# SparkFun_Qwiic_FS3000_top.net
KiCad netlist of a schematic drawn in EAGLE
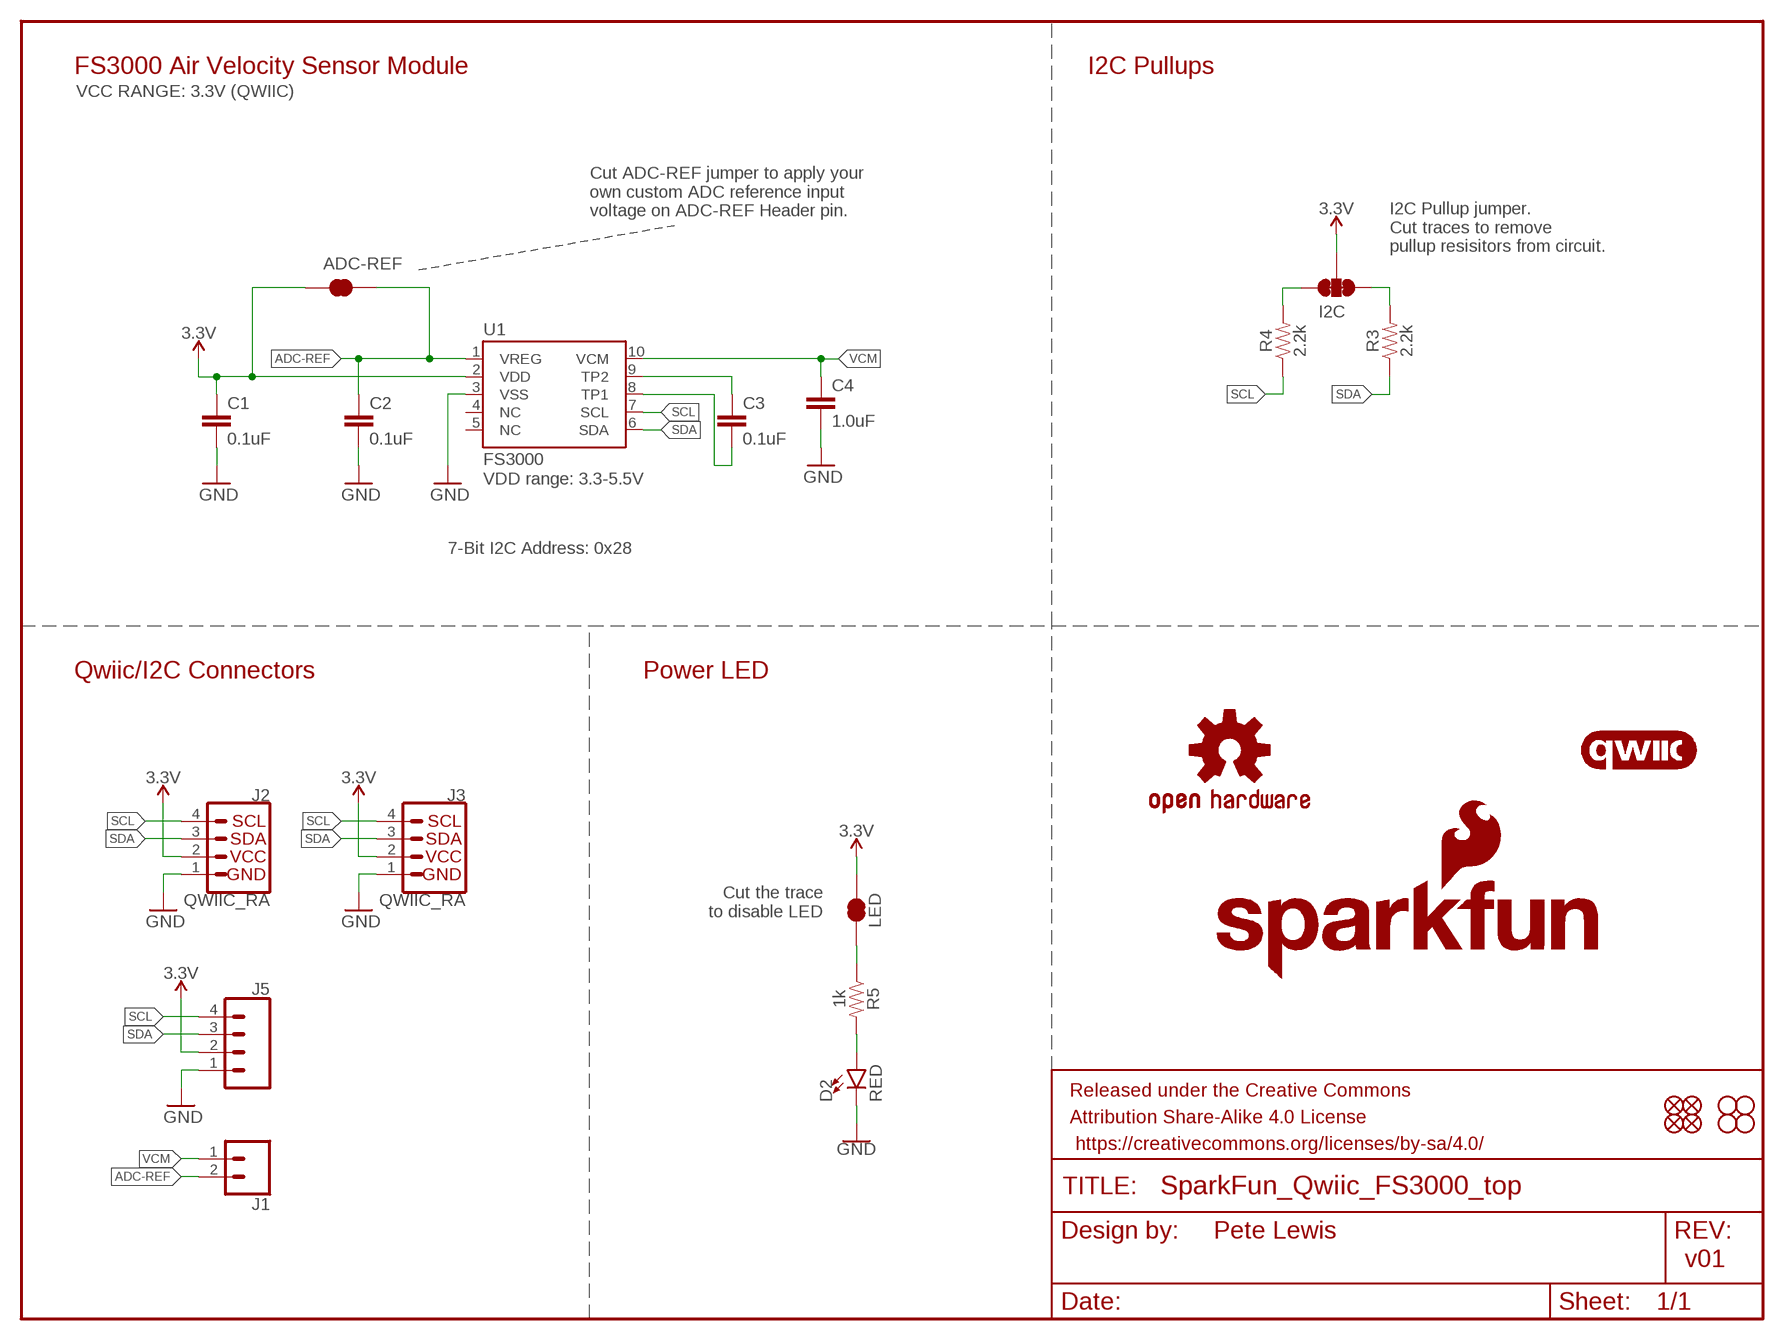
[diagram p0: schematic, sheet 1]

(export (version "E")
  (design (tool "Eeschema 10.0.6"))
  (components
    (comp (ref "ADC-REF")
      (value "JUMPER-SMT_2_NC_TRACE_SILK")
      (footprint "eagle-import:SMT-JUMPER_2_NC_TRACE_SILK")
      (libsource (lib "eagle-import") (part "JUMPER-SMT_2_NC_TRACE_SILK"))
    )
    (comp (ref "C1")
      (value "0.1uF")
      (footprint "eagle-import:0402-TIGHT")
      (libsource (lib "eagle-import") (part "0.1UF-0402T-16V-10%"))
    )
    (comp (ref "C2")
      (value "0.1uF")
      (footprint "eagle-import:0402-TIGHT")
      (libsource (lib "eagle-import") (part "0.1UF-0402T-16V-10%"))
    )
    (comp (ref "C3")
      (value "0.1uF")
      (footprint "eagle-import:0402-TIGHT")
      (libsource (lib "eagle-import") (part "0.1UF-0402T-16V-10%"))
    )
    (comp (ref "C4")
      (value "1.0uF")
      (footprint "eagle-import:0402-TIGHT")
      (libsource (lib "eagle-import") (part "1.0UF-0402T-16V-10%"))
    )
    (comp (ref "D2")
      (value "RED")
      (footprint "eagle-import:LED-0603")
      (libsource (lib "eagle-import") (part "LED-RED0603"))
    )
    (comp (ref "FRAME1")
      (value "FRAME-LETTER")
      (footprint "eagle-import:CREATIVE_COMMONS")
      (libsource (lib "eagle-import") (part "FRAME-LETTER"))
    )
    (comp (ref "I2C")
      (value "JUMPER-SMT_3_2-NC_TRACE_SILK")
      (footprint "eagle-import:SMT-JUMPER_3_2-NC_TRACE_SILK")
      (libsource (lib "eagle-import") (part "JUMPER-SMT_3_2-NC_TRACE_SILK"))
    )
    (comp (ref "J1")
      (value "CONN_021X02_NO_SILK")
      (footprint "eagle-import:1X02_NO_SILK")
      (libsource (lib "eagle-import") (part "CONN_021X02_NO_SILK"))
    )
    (comp (ref "J2")
      (value "QWIIC_RA")
      (footprint "eagle-import:JST04_1MM_RA")
      (libsource (lib "eagle-import") (part "QWIIC_CONNECTORJS-1MM"))
    )
    (comp (ref "J3")
      (value "QWIIC_RA")
      (footprint "eagle-import:JST04_1MM_RA")
      (libsource (lib "eagle-import") (part "QWIIC_CONNECTORJS-1MM"))
    )
    (comp (ref "J5")
      (value "CONN_041X04_NO_SILK")
      (footprint "eagle-import:1X04_NO_SILK")
      (libsource (lib "eagle-import") (part "CONN_041X04_NO_SILK"))
    )
    (comp (ref "JP1")
      (value "LED")
      (footprint "eagle-import:SMT-JUMPER_2_NC_TRACE_SILK")
      (libsource (lib "eagle-import") (part "JUMPER-SMT_2_NC_TRACE_SILK"))
    )
    (comp (ref "JP2")
      (value "FIDUCIALUFIDUCIAL")
      (footprint "eagle-import:MICRO-FIDUCIAL")
      (libsource (lib "eagle-import") (part "FIDUCIALUFIDUCIAL"))
    )
    (comp (ref "JP3")
      (value "STAND-OFF")
      (footprint "eagle-import:STAND-OFF")
      (libsource (lib "eagle-import") (part "STAND-OFF"))
    )
    (comp (ref "JP4")
      (value "STAND-OFF")
      (footprint "eagle-import:STAND-OFF")
      (libsource (lib "eagle-import") (part "STAND-OFF"))
    )
    (comp (ref "JP5")
      (value "FIDUCIALUFIDUCIAL")
      (footprint "eagle-import:MICRO-FIDUCIAL")
      (libsource (lib "eagle-import") (part "FIDUCIALUFIDUCIAL"))
    )
    (comp (ref "JP6")
      (value "FIDUCIALUFIDUCIAL")
      (footprint "eagle-import:MICRO-FIDUCIAL")
      (libsource (lib "eagle-import") (part "FIDUCIALUFIDUCIAL"))
    )
    (comp (ref "JP7")
      (value "STAND-OFF")
      (footprint "eagle-import:STAND-OFF")
      (libsource (lib "eagle-import") (part "STAND-OFF"))
    )
    (comp (ref "JP8")
      (value "STAND-OFF")
      (footprint "eagle-import:STAND-OFF")
      (libsource (lib "eagle-import") (part "STAND-OFF"))
    )
    (comp (ref "JP11")
      (value "FIDUCIALUFIDUCIAL")
      (footprint "eagle-import:MICRO-FIDUCIAL")
      (libsource (lib "eagle-import") (part "FIDUCIALUFIDUCIAL"))
    )
    (comp (ref "LOGO1")
      (value "OSHW-LOGOMINI")
      (footprint "eagle-import:OSHW-LOGO-MINI")
      (libsource (lib "eagle-import") (part "OSHW-LOGOMINI"))
    )
    (comp (ref "LOGO3")
      (value "SFE_LOGO_NAME_FLAME.1_INCH")
      (footprint "eagle-import:SFE_LOGO_NAME_FLAME_.1")
      (libsource (lib "eagle-import") (part "SFE_LOGO_NAME_FLAME.1_INCH"))
    )
    (comp (ref "LOGO4")
      (value "QWIIC_LOGO_5MM")
      (footprint "eagle-import:QWIIC_5MM")
      (libsource (lib "eagle-import") (part "QWIIC_LOGO_5MM"))
    )
    (comp (ref "LOGO5")
      (value "SFE_LOGO_NAME_FLAME.1_INCH")
      (footprint "eagle-import:SFE_LOGO_NAME_FLAME_.1")
      (libsource (lib "eagle-import") (part "SFE_LOGO_NAME_FLAME.1_INCH"))
    )
    (comp (ref "R3")
      (value "2.2k")
      (footprint "eagle-import:0402-TIGHT")
      (libsource (lib "eagle-import") (part "2.2KOHM-0402T-1/16W-1%"))
    )
    (comp (ref "R4")
      (value "2.2k")
      (footprint "eagle-import:0402-TIGHT")
      (libsource (lib "eagle-import") (part "2.2KOHM-0402T-1/16W-1%"))
    )
    (comp (ref "R5")
      (value "1k")
      (footprint "eagle-import:0402-TIGHT")
      (libsource (lib "eagle-import") (part "1KOHM-0402T-1/16W-1%"))
    )
    (comp (ref "U1")
      (value "FS3000")
      (footprint "eagle-import:FS3000")
      (libsource (lib "eagle-import") (part "FS3000"))
    )
  )
  (nets
    (net (code "1") (name "3.3V") (class "Default")
      (node (ref "ADC-REF") (pin "1") (pinfunction "1_1") (pintype "passive"))
      (node (ref "C1") (pin "1") (pinfunction "1_1") (pintype "passive"))
      (node (ref "I2C") (pin "2") (pinfunction "2_2") (pintype "passive"))
      (node (ref "J2") (pin "2") (pinfunction "2_2") (pintype "power_in"))
      (node (ref "J3") (pin "2") (pinfunction "2_2") (pintype "power_in"))
      (node (ref "J5") (pin "2") (pinfunction "2_2") (pintype "passive"))
      (node (ref "JP1") (pin "2") (pinfunction "2_2") (pintype "passive"))
      (node (ref "U1") (pin "2") (pinfunction "VDD_2") (pintype "bidirectional"))
    )
    (net (code "2") (name "ADC-REF") (class "Default")
      (node (ref "ADC-REF") (pin "2") (pinfunction "2_2") (pintype "passive"))
      (node (ref "C2") (pin "1") (pinfunction "1_1") (pintype "passive"))
      (node (ref "J1") (pin "2") (pinfunction "2_2") (pintype "passive"))
      (node (ref "U1") (pin "1") (pinfunction "VREG_1") (pintype "bidirectional"))
    )
    (net (code "3") (name "GND") (class "Default")
      (node (ref "C1") (pin "2") (pinfunction "2_2") (pintype "passive"))
      (node (ref "C2") (pin "2") (pinfunction "2_2") (pintype "passive"))
      (node (ref "C4") (pin "2") (pinfunction "2_2") (pintype "passive"))
      (node (ref "D2") (pin "C") (pinfunction "C_C") (pintype "passive"))
      (node (ref "J2") (pin "1") (pinfunction "1_1") (pintype "power_in"))
      (node (ref "J3") (pin "1") (pinfunction "1_1") (pintype "power_in"))
      (node (ref "J5") (pin "1") (pinfunction "1_1") (pintype "passive"))
      (node (ref "U1") (pin "3") (pinfunction "VSS_3") (pintype "bidirectional"))
    )
    (net (code "4") (name "Net-(D2-PadA)") (class "Default")
      (node (ref "D2") (pin "A") (pinfunction "A_A") (pintype "passive"))
      (node (ref "R5") (pin "2") (pinfunction "2_2") (pintype "passive"))
    )
    (net (code "5") (name "Net-(I2C-Pad1)") (class "Default")
      (node (ref "I2C") (pin "1") (pinfunction "1_1") (pintype "passive"))
      (node (ref "R3") (pin "2") (pinfunction "2_2") (pintype "passive"))
    )
    (net (code "6") (name "Net-(I2C-Pad3)") (class "Default")
      (node (ref "I2C") (pin "3") (pinfunction "3_3") (pintype "passive"))
      (node (ref "R4") (pin "2") (pinfunction "2_2") (pintype "passive"))
    )
    (net (code "7") (name "Net-(JP1-Pad1)") (class "Default")
      (node (ref "JP1") (pin "1") (pinfunction "1_1") (pintype "passive"))
      (node (ref "R5") (pin "1") (pinfunction "1_1") (pintype "passive"))
    )
    (net (code "8") (name "Net-(U1-TP1)") (class "Default")
      (node (ref "C3") (pin "2") (pinfunction "2_2") (pintype "passive"))
      (node (ref "U1") (pin "8") (pinfunction "TP1_8") (pintype "bidirectional"))
    )
    (net (code "9") (name "Net-(U1-TP2)") (class "Default")
      (node (ref "C3") (pin "1") (pinfunction "1_1") (pintype "passive"))
      (node (ref "U1") (pin "9") (pinfunction "TP2_9") (pintype "bidirectional"))
    )
    (net (code "10") (name "SCL") (class "Default")
      (node (ref "J2") (pin "4") (pinfunction "4_4") (pintype "passive"))
      (node (ref "J3") (pin "4") (pinfunction "4_4") (pintype "passive"))
      (node (ref "J5") (pin "4") (pinfunction "4_4") (pintype "passive"))
      (node (ref "R4") (pin "1") (pinfunction "1_1") (pintype "passive"))
      (node (ref "U1") (pin "7") (pinfunction "SCL_7") (pintype "bidirectional"))
    )
    (net (code "11") (name "SDA") (class "Default")
      (node (ref "J2") (pin "3") (pinfunction "3_3") (pintype "passive"))
      (node (ref "J3") (pin "3") (pinfunction "3_3") (pintype "passive"))
      (node (ref "J5") (pin "3") (pinfunction "3_3") (pintype "passive"))
      (node (ref "R3") (pin "1") (pinfunction "1_1") (pintype "passive"))
      (node (ref "U1") (pin "6") (pinfunction "SDA_6") (pintype "bidirectional"))
    )
    (net (code "12") (name "VCM") (class "Default")
      (node (ref "C4") (pin "1") (pinfunction "1_1") (pintype "passive"))
      (node (ref "J1") (pin "1") (pinfunction "1_1") (pintype "passive"))
      (node (ref "U1") (pin "10") (pinfunction "VCM_10") (pintype "bidirectional"))
    )
    (net (code "13") (name "unconnected-(U1-NC-Pad4)") (class "Default")
      (node (ref "U1") (pin "4") (pinfunction "NC_4") (pintype "no_connect"))
    )
    (net (code "14") (name "unconnected-(U1-NC-Pad5)") (class "Default")
      (node (ref "U1") (pin "5") (pinfunction "NC_5") (pintype "no_connect"))
    )
  )
)
